# fabTinyStar-013.net
KiCad netlist of a schematic drawn in EAGLE
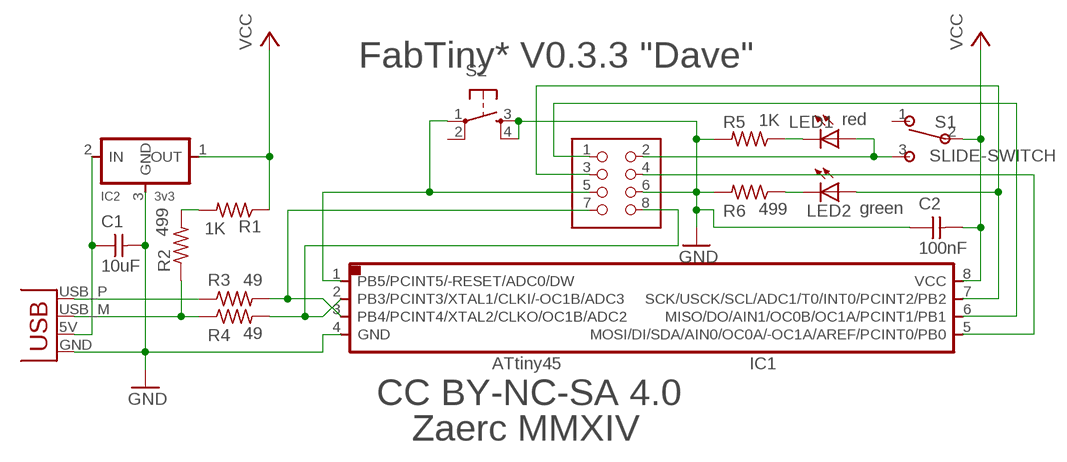
[diagram p0: schematic, sheet 1]

(export (version "E")
  (design (tool "Eeschema 10.0.6"))
  (components
    (comp (ref "C1")
      (value "10uF")
      (footprint "eagle-import:1206")
      (libsource (lib "eagle-import") (part "UNPOLARIZED_CAPACITOR1206"))
    )
    (comp (ref "C2")
      (value "100nF")
      (footprint "eagle-import:1206")
      (libsource (lib "eagle-import") (part "UNPOLARIZED_CAPACITOR1206"))
    )
    (comp (ref "IC1")
      (value "ATTINY*5")
      (footprint "eagle-import:SOIC8")
      (libsource (lib "eagle-import") (part "ATTINY45SI"))
    )
    (comp (ref "IC2")
      (value "3v3")
      (footprint "eagle-import:SOT23")
      (libsource (lib "eagle-import") (part "REGULATORSOT23"))
    )
    (comp (ref "JP1")
      (value "PINHD-2X04")
      (footprint "eagle-import:54202-G0808LF")
      (libsource (lib "eagle-import") (part "PINHD-2X04"))
    )
    (comp (ref "LED1")
      (value "red")
      (footprint "eagle-import:1206")
      (libsource (lib "eagle-import") (part "LEDSMT1206"))
    )
    (comp (ref "LED2")
      (value "green")
      (footprint "eagle-import:1206")
      (libsource (lib "eagle-import") (part "LEDSMT1206"))
    )
    (comp (ref "R1")
      (value "1K")
      (footprint "eagle-import:1206")
      (libsource (lib "eagle-import") (part "RESISTOR1206"))
    )
    (comp (ref "R2")
      (value "499")
      (footprint "eagle-import:1206")
      (libsource (lib "eagle-import") (part "RESISTOR1206"))
    )
    (comp (ref "R3")
      (value "49")
      (footprint "eagle-import:1206")
      (libsource (lib "eagle-import") (part "RESISTOR1206"))
    )
    (comp (ref "R4")
      (value "49")
      (footprint "eagle-import:1206")
      (libsource (lib "eagle-import") (part "RESISTOR1206"))
    )
    (comp (ref "R5")
      (value "1K")
      (footprint "eagle-import:1206")
      (libsource (lib "eagle-import") (part "RESISTOR1206"))
    )
    (comp (ref "R6")
      (value "499")
      (footprint "eagle-import:1206")
      (libsource (lib "eagle-import") (part "RESISTOR1206"))
    )
    (comp (ref "S1")
      (value "SLIDE-SWITCH")
      (footprint "eagle-import:AYZ0102AGRLC")
      (libsource (lib "eagle-import") (part "SLIDE-SWITCH"))
    )
    (comp (ref "S2")
      (value "6MM_SWITCH6MM_SWITCH")
      (footprint "eagle-import:6MM_SWITCH")
      (libsource (lib "eagle-import") (part "6MM_SWITCH6MM_SWITCH"))
    )
    (comp (ref "USB")
      (value "USBPCB")
      (footprint "eagle-import:USB-A-PCB")
      (libsource (lib "eagle-import") (part "USBPCB"))
    )
  )
  (nets
    (net (code "1") (name "GND") (class "Default")
      (node (ref "C1") (pin "2") (pinfunction "2_2") (pintype "passive"))
      (node (ref "C2") (pin "1") (pinfunction "1_1") (pintype "passive"))
      (node (ref "IC1") (pin "4") (pinfunction "GND_4") (pintype "bidirectional"))
      (node (ref "IC2") (pin "3") (pinfunction "GND_3") (pintype "bidirectional"))
      (node (ref "JP1") (pin "6") (pinfunction "6_6") (pintype "passive"))
      (node (ref "R5") (pin "2") (pinfunction "2_2") (pintype "passive"))
      (node (ref "R6") (pin "2") (pinfunction "2_2") (pintype "passive"))
      (node (ref "S2") (pin "3") (pinfunction "S_3") (pintype "passive"))
      (node (ref "S2") (pin "4") (pinfunction "S1_4") (pintype "passive"))
      (node (ref "USB") (pin "GND") (pinfunction "GND_GND") (pintype "bidirectional"))
    )
    (net (code "2") (name "Net-(IC1-MISO{slash}DO{slash}AIN1{slash}OC0B{slash}OC1A{slash}PCINT1{slash}PB1)") (class "Default")
      (node (ref "IC1") (pin "6") (pinfunction "MISO/DO/AIN1/OC0B/OC1A/PCINT1/PB1_6") (pintype "bidirectional"))
      (node (ref "JP1") (pin "1") (pinfunction "1_1") (pintype "passive"))
    )
    (net (code "3") (name "Net-(IC1-MOSI{slash}DI{slash}SDA{slash}AIN0{slash}OC0A{slash}-OC1A{slash}AREF{slash}PCINT0{slash}PB0)") (class "Default")
      (node (ref "IC1") (pin "5") (pinfunction "MOSI/DI/SDA/AIN0/OC0A/-OC1A/AREF/PCINT0/PB0_5") (pintype "bidirectional"))
      (node (ref "JP1") (pin "4") (pinfunction "4_4") (pintype "passive"))
    )
    (net (code "4") (name "Net-(IC1-PB3{slash}PCINT3{slash}XTAL1{slash}CLKI{slash}-OC1B{slash}ADC3)") (class "Default")
      (node (ref "IC1") (pin "2") (pinfunction "PB3/PCINT3/XTAL1/CLKI/-OC1B/ADC3_2") (pintype "bidirectional"))
      (node (ref "JP1") (pin "8") (pinfunction "8_8") (pintype "passive"))
      (node (ref "R4") (pin "2") (pinfunction "2_2") (pintype "passive"))
    )
    (net (code "5") (name "Net-(IC1-PB4{slash}PCINT4{slash}XTAL2{slash}CLKO{slash}OC1B{slash}ADC2)") (class "Default")
      (node (ref "IC1") (pin "3") (pinfunction "PB4/PCINT4/XTAL2/CLKO/OC1B/ADC2_3") (pintype "bidirectional"))
      (node (ref "JP1") (pin "7") (pinfunction "7_7") (pintype "passive"))
      (node (ref "R3") (pin "2") (pinfunction "2_2") (pintype "passive"))
    )
    (net (code "6") (name "Net-(IC1-PB5{slash}PCINT5{slash}-RESET{slash}ADC0{slash}DW)") (class "Default")
      (node (ref "IC1") (pin "1") (pinfunction "PB5/PCINT5/-RESET/ADC0/DW_1") (pintype "bidirectional"))
      (node (ref "JP1") (pin "5") (pinfunction "5_5") (pintype "passive"))
      (node (ref "S2") (pin "1") (pinfunction "P_1") (pintype "passive"))
    )
    (net (code "7") (name "Net-(IC1-SCK{slash}USCK{slash}SCL{slash}ADC1{slash}T0{slash}INT0{slash}PCINT2{slash}PB2)") (class "Default")
      (node (ref "IC1") (pin "7") (pinfunction "SCK/USCK/SCL/ADC1/T0/INT0/PCINT2/PB2_7") (pintype "bidirectional"))
      (node (ref "JP1") (pin "3") (pinfunction "3_3") (pintype "passive"))
      (node (ref "LED2") (pin "A") (pinfunction "A_A") (pintype "passive"))
    )
    (net (code "8") (name "Net-(IC2-IN)") (class "Default")
      (node (ref "C1") (pin "1") (pinfunction "1_1") (pintype "passive"))
      (node (ref "IC2") (pin "2") (pinfunction "IN_2") (pintype "bidirectional"))
      (node (ref "USB") (pin "5V") (pinfunction "VBUS_5V") (pintype "bidirectional"))
    )
    (net (code "9") (name "Net-(JP1-Pad2)") (class "Default")
      (node (ref "JP1") (pin "2") (pinfunction "2_2") (pintype "passive"))
      (node (ref "LED1") (pin "A") (pinfunction "A_A") (pintype "passive"))
      (node (ref "S1") (pin "3") (pinfunction "3_3") (pintype "bidirectional"))
    )
    (net (code "10") (name "Net-(LED1-PadC)") (class "Default")
      (node (ref "LED1") (pin "C") (pinfunction "C_C") (pintype "passive"))
      (node (ref "R5") (pin "1") (pinfunction "1_1") (pintype "passive"))
    )
    (net (code "11") (name "Net-(LED2-PadC)") (class "Default")
      (node (ref "LED2") (pin "C") (pinfunction "C_C") (pintype "passive"))
      (node (ref "R6") (pin "1") (pinfunction "1_1") (pintype "passive"))
    )
    (net (code "12") (name "Net-(R1-Pad2)") (class "Default")
      (node (ref "R1") (pin "2") (pinfunction "2_2") (pintype "passive"))
      (node (ref "R2") (pin "2") (pinfunction "2_2") (pintype "passive"))
    )
    (net (code "13") (name "Net-(USB-D+)") (class "Default")
      (node (ref "R3") (pin "1") (pinfunction "1_1") (pintype "passive"))
      (node (ref "USB") (pin "USB_P") (pinfunction "D+_USB_P") (pintype "bidirectional"))
    )
    (net (code "14") (name "Net-(USB-D-)") (class "Default")
      (node (ref "R2") (pin "1") (pinfunction "1_1") (pintype "passive"))
      (node (ref "R4") (pin "1") (pinfunction "1_1") (pintype "passive"))
      (node (ref "USB") (pin "USB_M") (pinfunction "D-_USB_M") (pintype "bidirectional"))
    )
    (net (code "15") (name "VCC") (class "Default")
      (node (ref "C2") (pin "2") (pinfunction "2_2") (pintype "passive"))
      (node (ref "IC1") (pin "8") (pinfunction "VCC_8") (pintype "bidirectional"))
      (node (ref "IC2") (pin "1") (pinfunction "OUT_1") (pintype "bidirectional"))
      (node (ref "R1") (pin "1") (pinfunction "1_1") (pintype "passive"))
      (node (ref "S1") (pin "2") (pinfunction "2_2") (pintype "bidirectional"))
    )
    (net (code "16") (name "unconnected-(S1-Pad1)") (class "Default")
      (node (ref "S1") (pin "1") (pinfunction "1_1") (pintype "bidirectional"))
    )
    (net (code "17") (name "unconnected-(S2-P1-Pad2)") (class "Default")
      (node (ref "S2") (pin "2") (pinfunction "P1_2") (pintype "passive"))
    )
  )
)
